# Board.net
KiCad netlist of a schematic drawn in EAGLE
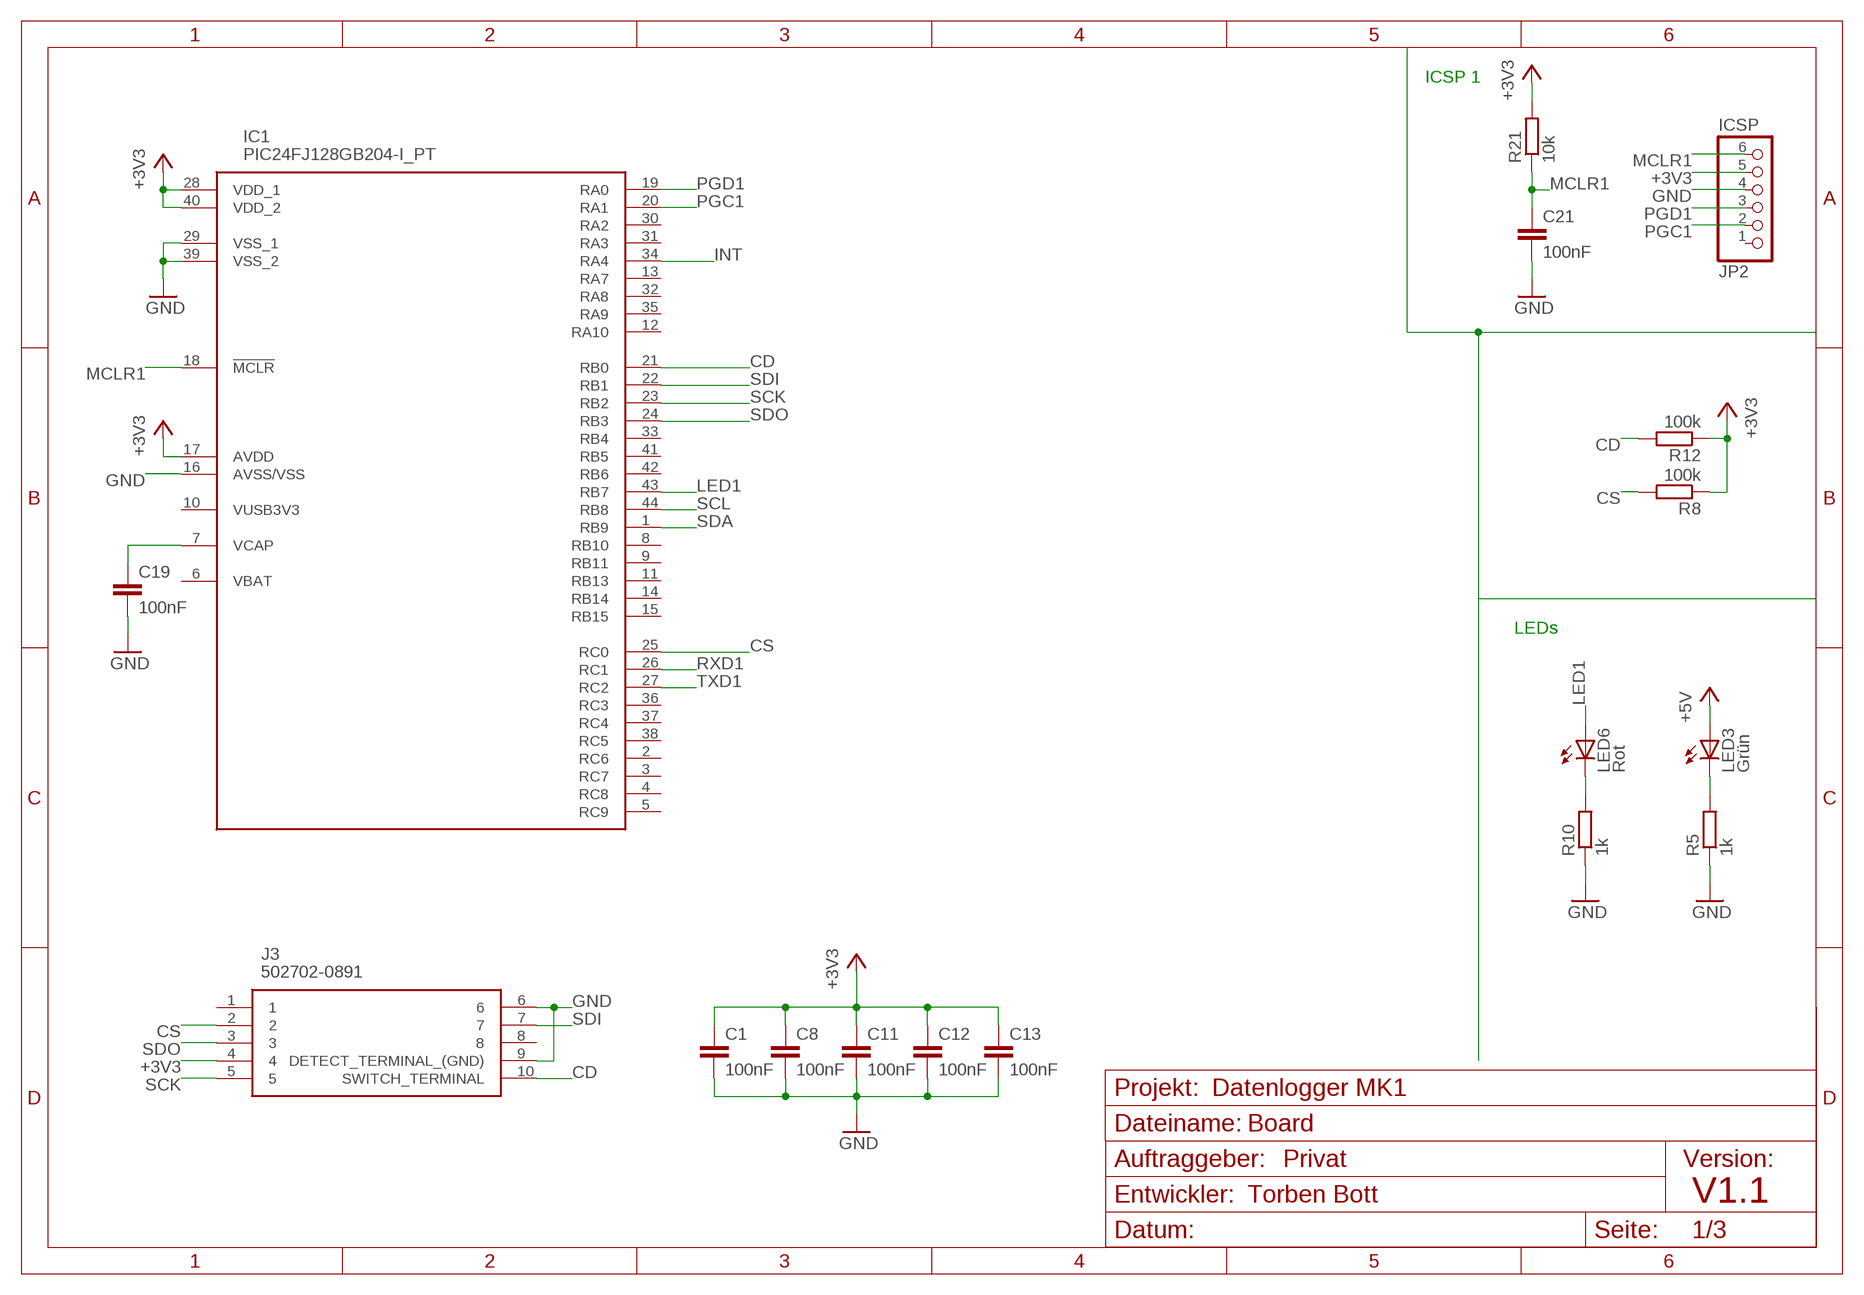
[diagram p0: schematic, sheet 1]
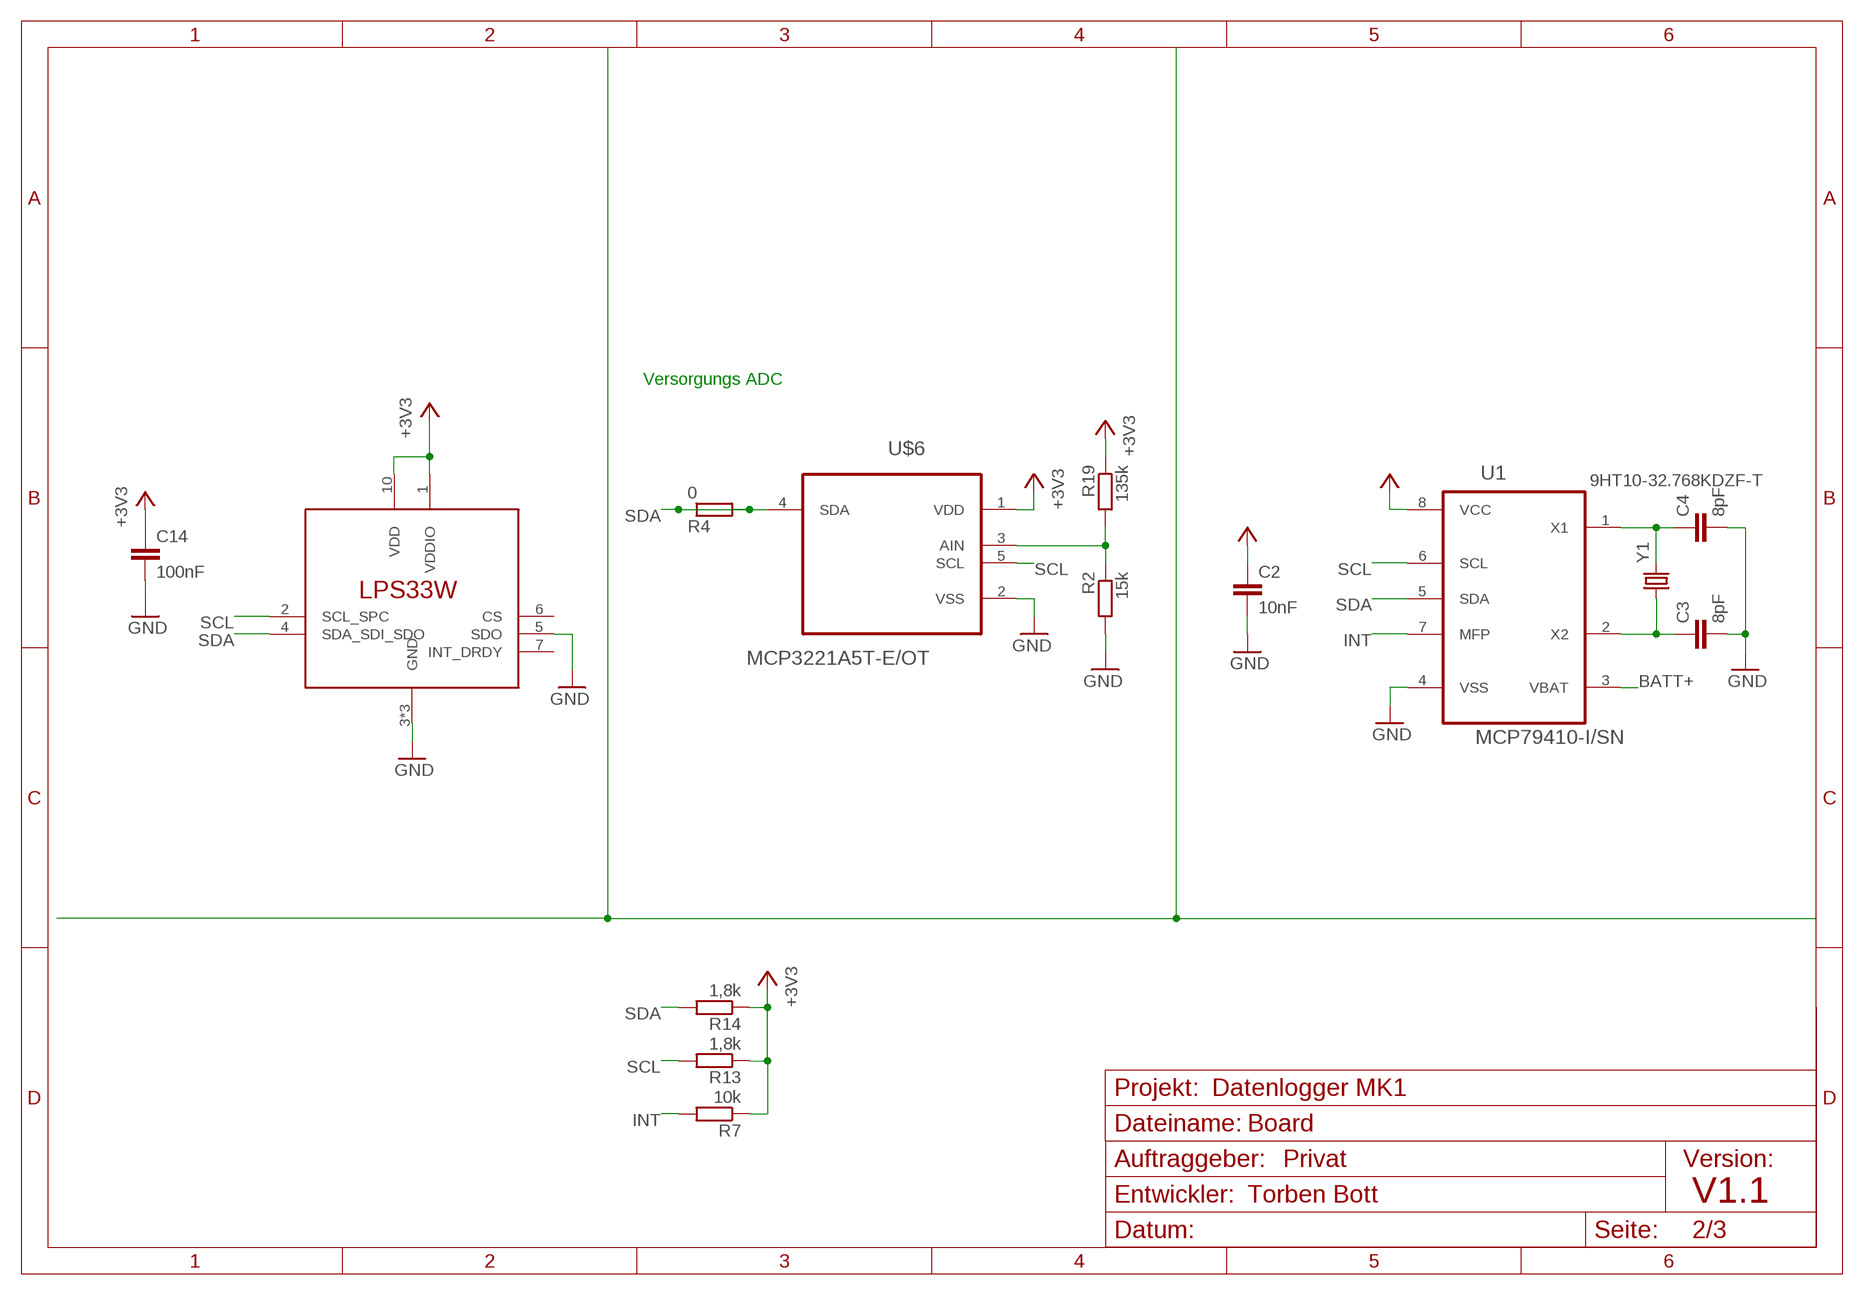
[diagram p1: schematic, sheet 2]
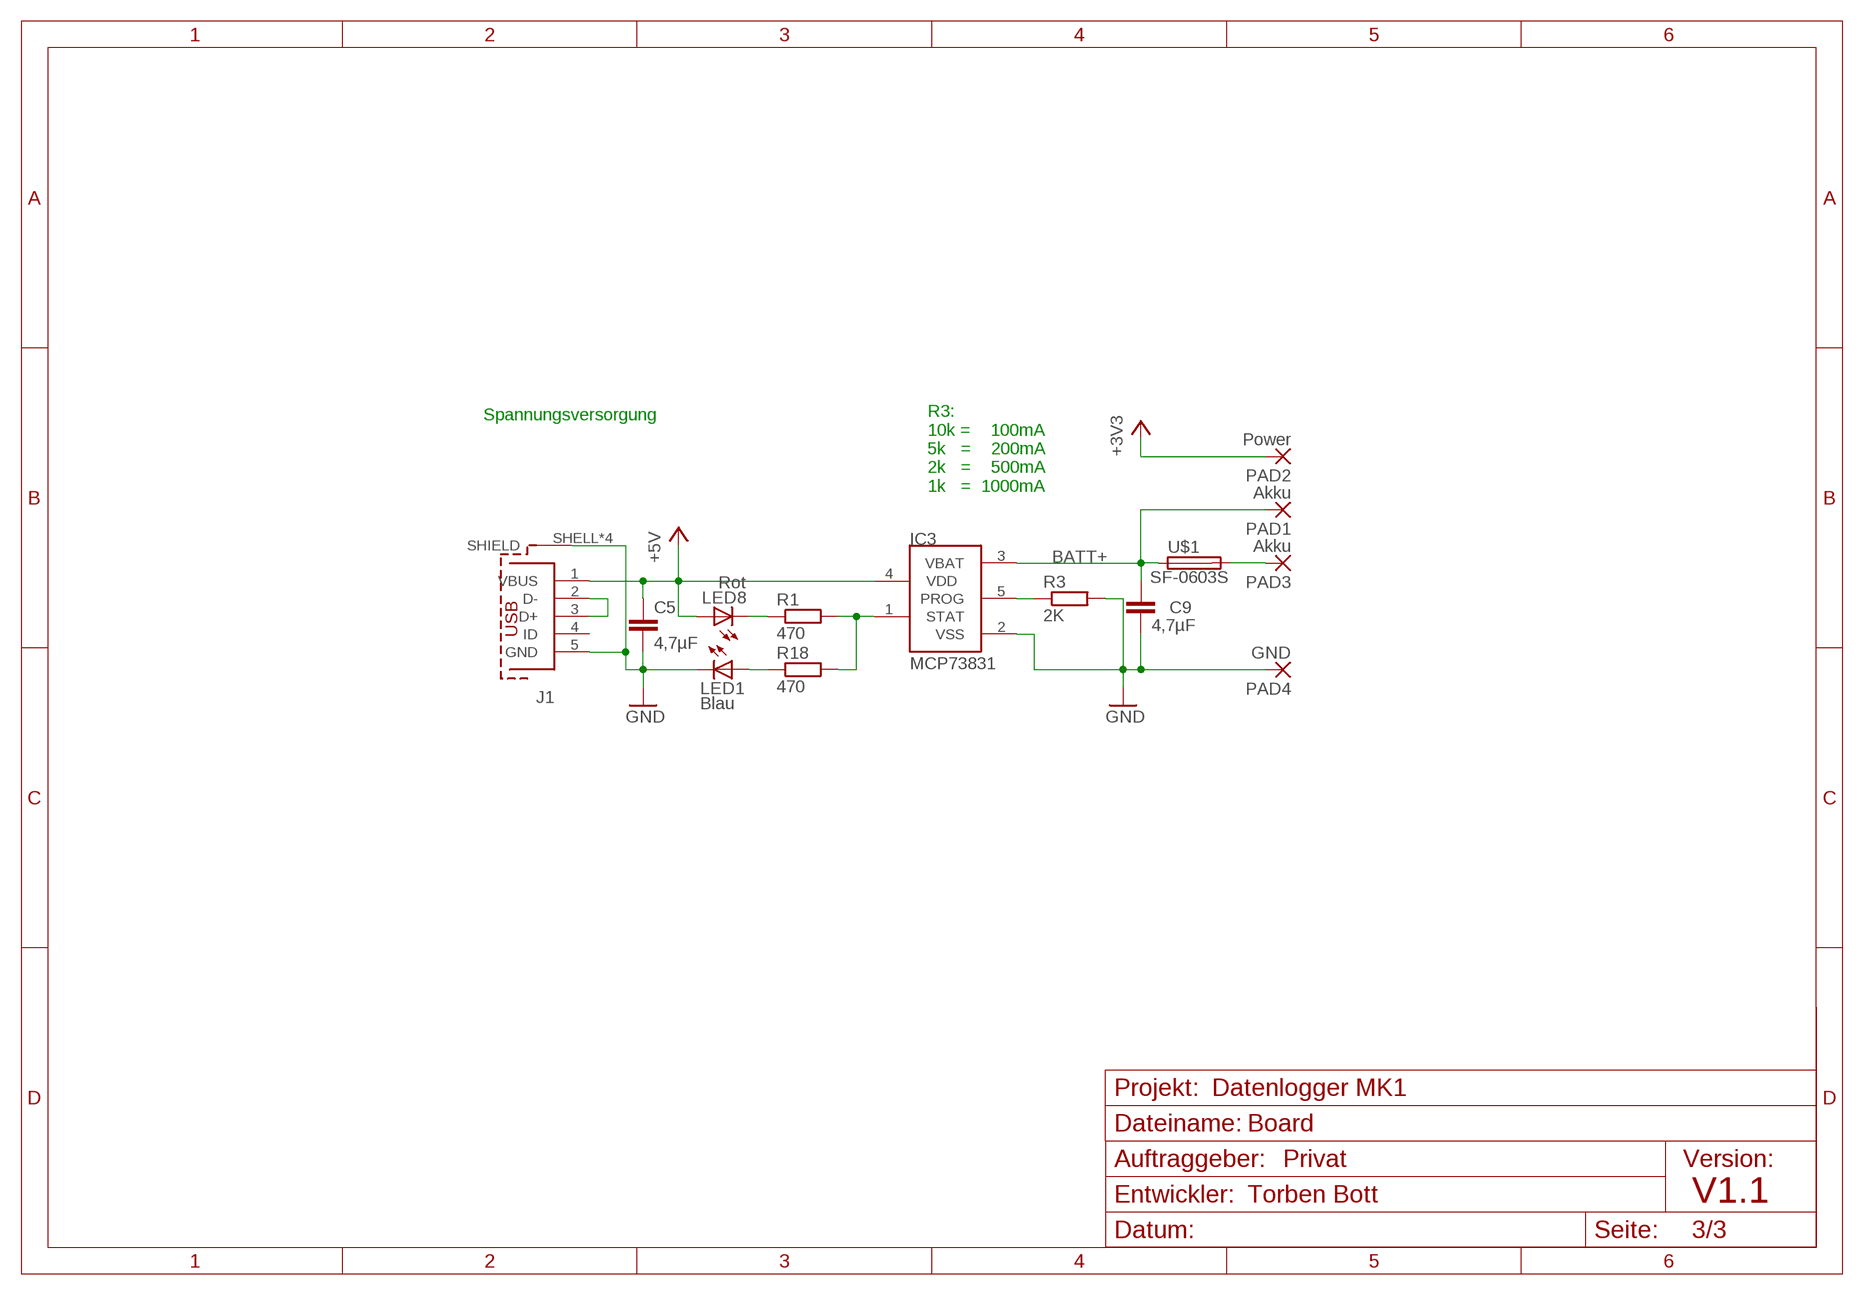
[diagram p2: schematic, sheet 3]

(export (version "E")
  (design (tool "Eeschema 10.0.6"))
  (components
    (comp (ref "C1")
      (value "100nF")
      (footprint "eagle-import:C0805")
      (libsource (lib "eagle-import") (part "rcl_334_C-EUC0805"))
    )
    (comp (ref "C8")
      (value "100nF")
      (footprint "eagle-import:C0805")
      (libsource (lib "eagle-import") (part "rcl_334_C-EUC0805"))
    )
    (comp (ref "C11")
      (value "100nF")
      (footprint "eagle-import:C0805")
      (libsource (lib "eagle-import") (part "rcl_334_C-EUC0805"))
    )
    (comp (ref "C12")
      (value "100nF")
      (footprint "eagle-import:C0805")
      (libsource (lib "eagle-import") (part "rcl_334_C-EUC0805"))
    )
    (comp (ref "C13")
      (value "100nF")
      (footprint "eagle-import:C0805")
      (libsource (lib "eagle-import") (part "rcl_334_C-EUC0805"))
    )
    (comp (ref "C19")
      (value "100nF")
      (footprint "eagle-import:C0805")
      (libsource (lib "eagle-import") (part "rcl_334_C-EUC0805"))
    )
    (comp (ref "C21")
      (value "100nF")
      (footprint "eagle-import:C0805")
      (libsource (lib "eagle-import") (part "rcl_334_C-EUC0805"))
    )
    (comp (ref "IC1")
      (value "PIC24FJ128GB204-I_PT")
      (footprint "eagle-import:QFP80P1200X1200X120-44N")
      (fields
        (field (name "MANUFACTURER_PART_NUMBER") "PIC24FJ128GB204-I/PT")
        (field (name "MOUSER_PART_NUMBER") "579-P24FJ128GB204IPT")
      )
      (libsource (lib "eagle-import") (part "PIC24FJ128GB204-I_PT"))
    )
    (comp (ref "J3")
      (value "502702-0891")
      (footprint "eagle-import:502702-0891")
      (fields (field (name "MOUSER_PART_NUMBER") "538-502702-0891"))
      (libsource (lib "eagle-import") (part "502702-0891"))
    )
    (comp (ref "JP2")
      (value "ICSP")
      (footprint "eagle-import:1X06_90")
      (libsource (lib "eagle-import") (part "PINHD-1X6/90"))
    )
    (comp (ref "LED3")
      (value "Grün")
      (footprint "eagle-import:CHIPLED_0805")
      (libsource (lib "eagle-import") (part "led_259_LEDCHIPLED_0805"))
    )
    (comp (ref "LED6")
      (value "Rot")
      (footprint "eagle-import:CHIPLED_0805")
      (libsource (lib "eagle-import") (part "led_259_LEDCHIPLED_0805"))
    )
    (comp (ref "R5")
      (value "1k")
      (footprint "eagle-import:R0805")
      (libsource (lib "eagle-import") (part "rcl_334_R-EU_R0805"))
    )
    (comp (ref "R8")
      (value "100k")
      (footprint "eagle-import:R0805")
      (libsource (lib "eagle-import") (part "rcl_334_R-EU_R0805"))
    )
    (comp (ref "R10")
      (value "1k")
      (footprint "eagle-import:R0805")
      (libsource (lib "eagle-import") (part "rcl_334_R-EU_R0805"))
    )
    (comp (ref "R12")
      (value "100k")
      (footprint "eagle-import:R0805")
      (libsource (lib "eagle-import") (part "rcl_334_R-EU_R0805"))
    )
    (comp (ref "R21")
      (value "10k")
      (footprint "eagle-import:R0805")
      (libsource (lib "eagle-import") (part "rcl_334_R-EU_R0805"))
    )
    (comp (ref "C2")
      (value "10nF")
      (footprint "eagle-import:C0805")
      (libsource (lib "eagle-import") (part "rcl_334_C-EUC0805"))
    )
    (comp (ref "C3")
      (value "8pF")
      (footprint "eagle-import:C0805")
      (libsource (lib "eagle-import") (part "rcl_334_C-EUC0805"))
    )
    (comp (ref "C4")
      (value "8pF")
      (footprint "eagle-import:C0805")
      (libsource (lib "eagle-import") (part "rcl_334_C-EUC0805"))
    )
    (comp (ref "C14")
      (value "100nF")
      (footprint "eagle-import:C0805")
      (libsource (lib "eagle-import") (part "rcl_334_C-EUC0805"))
    )
    (comp (ref "R2")
      (value "15k")
      (footprint "eagle-import:R0805")
      (libsource (lib "eagle-import") (part "rcl_334_R-EU_R0805"))
    )
    (comp (ref "R4")
      (value "0")
      (footprint "eagle-import:R0805")
      (libsource (lib "eagle-import") (part "rcl_334_R-EU_R0805"))
    )
    (comp (ref "R7")
      (value "10k")
      (footprint "eagle-import:R0805")
      (libsource (lib "eagle-import") (part "rcl_334_R-EU_R0805"))
    )
    (comp (ref "R13")
      (value "1,8k")
      (footprint "eagle-import:R0805")
      (libsource (lib "eagle-import") (part "rcl_334_R-EU_R0805"))
    )
    (comp (ref "R14")
      (value "1,8k")
      (footprint "eagle-import:R0805")
      (libsource (lib "eagle-import") (part "rcl_334_R-EU_R0805"))
    )
    (comp (ref "R19")
      (value "135k")
      (footprint "eagle-import:R0805")
      (libsource (lib "eagle-import") (part "rcl_334_R-EU_R0805"))
    )
    (comp (ref "U$6")
      (value "MCP3221A5T-E/OT")
      (footprint "eagle-import:SOT95P270X145-5N")
      (libsource (lib "eagle-import") (part "MCP3221A5T-E/OT"))
    )
    (comp (ref "U$7")
      (value "LPS33W")
      (footprint "eagle-import:CCLGA10L")
      (libsource (lib "eagle-import") (part "LPS33W"))
    )
    (comp (ref "U1")
      (value "MCP79410-I/SN")
      (footprint "eagle-import:SOIC127P600X175-8N")
      (fields (field (name "MPN") "MCP79410-I/SN "))
      (libsource (lib "eagle-import") (part "MCP79410-I/SN"))
    )
    (comp (ref "Y1")
      (value "9HT10-32.768KDZF-T")
      (footprint "eagle-import:9HT1032768KEZFT")
      (fields (field (name "MOUSER_PART_NUMBER") "717-9HT10-32.768KDZF"))
      (libsource (lib "eagle-import") (part "9HT10-32.768KDZF-T"))
    )
    (comp (ref "C5")
      (value "4,7µF")
      (footprint "eagle-import:C0805")
      (libsource (lib "eagle-import") (part "C-EUC0805"))
    )
    (comp (ref "C9")
      (value "4,7µF")
      (footprint "eagle-import:C0805")
      (libsource (lib "eagle-import") (part "C-EUC0805"))
    )
    (comp (ref "IC3")
      (value "MCP73831")
      (footprint "eagle-import:SOT23-5L")
      (libsource (lib "eagle-import") (part "MCP73831"))
    )
    (comp (ref "J1")
      (value "629105136821")
      (footprint "eagle-import:629105136821")
      (libsource (lib "eagle-import") (part "629105136821"))
    )
    (comp (ref "LED1")
      (value "Blau")
      (footprint "eagle-import:CHIPLED_0805")
      (libsource (lib "eagle-import") (part "LEDCHIPLED_0805"))
    )
    (comp (ref "LED8")
      (value "Rot")
      (footprint "eagle-import:CHIPLED_0805")
      (libsource (lib "eagle-import") (part "LEDCHIPLED_0805"))
    )
    (comp (ref "PAD1")
      (value "Akku")
      (footprint "eagle-import:5-1,8")
      (libsource (lib "eagle-import") (part "WIREPADSMD5-1,8"))
    )
    (comp (ref "PAD2")
      (value "Power")
      (footprint "eagle-import:5-1,8")
      (libsource (lib "eagle-import") (part "WIREPADSMD5-1,8"))
    )
    (comp (ref "PAD3")
      (value "Akku")
      (footprint "eagle-import:5-1,8")
      (libsource (lib "eagle-import") (part "WIREPADSMD5-1,8"))
    )
    (comp (ref "PAD4")
      (value "GND")
      (footprint "eagle-import:5-1,8")
      (libsource (lib "eagle-import") (part "WIREPADSMD5-1,8"))
    )
    (comp (ref "R1")
      (value "470")
      (footprint "eagle-import:R0805")
      (libsource (lib "eagle-import") (part "R-EU_R0805"))
    )
    (comp (ref "R3")
      (value "2K")
      (footprint "eagle-import:R0805")
      (libsource (lib "eagle-import") (part "R-EU_R0805"))
    )
    (comp (ref "R18")
      (value "470")
      (footprint "eagle-import:R0805")
      (libsource (lib "eagle-import") (part "R-EU_R0805"))
    )
    (comp (ref "U$1")
      (value "SF-0603S")
      (footprint "eagle-import:R0603")
      (libsource (lib "eagle-import") (part "SF-0603S"))
    )
  )
  (nets
    (net (code "1") (name "+3V3") (class "Default")
      (node (ref "C1") (pin "1") (pinfunction "1_1") (pintype "passive"))
      (node (ref "C11") (pin "1") (pinfunction "1_1") (pintype "passive"))
      (node (ref "C12") (pin "1") (pinfunction "1_1") (pintype "passive"))
      (node (ref "C13") (pin "1") (pinfunction "1_1") (pintype "passive"))
      (node (ref "C14") (pin "1") (pinfunction "1_1") (pintype "passive"))
      (node (ref "C2") (pin "1") (pinfunction "1_1") (pintype "passive"))
      (node (ref "C8") (pin "1") (pinfunction "1_1") (pintype "passive"))
      (node (ref "IC1") (pin "17") (pinfunction "AVDD_17") (pintype "power_in"))
      (node (ref "IC1") (pin "28") (pinfunction "VDD_1_28") (pintype "power_in"))
      (node (ref "IC1") (pin "40") (pinfunction "VDD_2_40") (pintype "power_in"))
      (node (ref "J3") (pin "4") (pinfunction "4_4") (pintype "bidirectional"))
      (node (ref "JP2") (pin "5") (pinfunction "5_5") (pintype "passive"))
      (node (ref "PAD2") (pin "1") (pinfunction "P_1") (pintype "passive"))
      (node (ref "R12") (pin "1") (pinfunction "1_1") (pintype "passive"))
      (node (ref "R13") (pin "1") (pinfunction "1_1") (pintype "passive"))
      (node (ref "R14") (pin "1") (pinfunction "1_1") (pintype "passive"))
      (node (ref "R19") (pin "1") (pinfunction "1_1") (pintype "passive"))
      (node (ref "R21") (pin "2") (pinfunction "2_2") (pintype "passive"))
      (node (ref "R7") (pin "1") (pinfunction "1_1") (pintype "passive"))
      (node (ref "R8") (pin "1") (pinfunction "1_1") (pintype "passive"))
      (node (ref "U$6") (pin "1") (pinfunction "VDD_1") (pintype "power_in"))
      (node (ref "U$7") (pin "1") (pinfunction "VDDIO_1") (pintype "power_in"))
      (node (ref "U$7") (pin "10") (pinfunction "VDD_10") (pintype "power_in"))
      (node (ref "U1") (pin "8") (pinfunction "VCC_8") (pintype "power_in"))
    )
    (net (code "2") (name "+5V") (class "Default")
      (node (ref "C5") (pin "1") (pinfunction "1_1") (pintype "passive"))
      (node (ref "IC3") (pin "4") (pinfunction "VDD_4") (pintype "bidirectional"))
      (node (ref "J1") (pin "1") (pinfunction "VBUS_1") (pintype "passive"))
      (node (ref "LED3") (pin "A") (pinfunction "A_A") (pintype "passive"))
      (node (ref "LED8") (pin "A") (pinfunction "A_A") (pintype "passive"))
    )
    (net (code "3") (name "BATT+") (class "Default")
      (node (ref "C9") (pin "1") (pinfunction "1_1") (pintype "passive"))
      (node (ref "IC3") (pin "3") (pinfunction "VBAT_3") (pintype "bidirectional"))
      (node (ref "PAD1") (pin "1") (pinfunction "P_1") (pintype "passive"))
      (node (ref "U$1") (pin "1") (pinfunction "1_1") (pintype "passive"))
      (node (ref "U1") (pin "3") (pinfunction "VBAT_3") (pintype "power_in"))
    )
    (net (code "4") (name "CD") (class "Default")
      (node (ref "IC1") (pin "21") (pinfunction "RB0_21") (pintype "bidirectional"))
      (node (ref "J3") (pin "10") (pinfunction "SWITCH_TERMINAL_10") (pintype "bidirectional"))
      (node (ref "R12") (pin "2") (pinfunction "2_2") (pintype "passive"))
    )
    (net (code "5") (name "CS") (class "Default")
      (node (ref "IC1") (pin "25") (pinfunction "RC0_25") (pintype "bidirectional"))
      (node (ref "J3") (pin "2") (pinfunction "2_2") (pintype "bidirectional"))
      (node (ref "R8") (pin "2") (pinfunction "2_2") (pintype "passive"))
    )
    (net (code "6") (name "GND") (class "Default")
      (node (ref "C1") (pin "2") (pinfunction "2_2") (pintype "passive"))
      (node (ref "C11") (pin "2") (pinfunction "2_2") (pintype "passive"))
      (node (ref "C12") (pin "2") (pinfunction "2_2") (pintype "passive"))
      (node (ref "C13") (pin "2") (pinfunction "2_2") (pintype "passive"))
      (node (ref "C14") (pin "2") (pinfunction "2_2") (pintype "passive"))
      (node (ref "C19") (pin "2") (pinfunction "2_2") (pintype "passive"))
      (node (ref "C2") (pin "2") (pinfunction "2_2") (pintype "passive"))
      (node (ref "C21") (pin "2") (pinfunction "2_2") (pintype "passive"))
      (node (ref "C3") (pin "2") (pinfunction "2_2") (pintype "passive"))
      (node (ref "C4") (pin "2") (pinfunction "2_2") (pintype "passive"))
      (node (ref "C5") (pin "2") (pinfunction "2_2") (pintype "passive"))
      (node (ref "C8") (pin "2") (pinfunction "2_2") (pintype "passive"))
      (node (ref "C9") (pin "2") (pinfunction "2_2") (pintype "passive"))
      (node (ref "IC1") (pin "16") (pinfunction "AVSS/VSS_16") (pintype "power_in"))
      (node (ref "IC1") (pin "29") (pinfunction "VSS_1_29") (pintype "power_in"))
      (node (ref "IC1") (pin "39") (pinfunction "VSS_2_39") (pintype "power_in"))
      (node (ref "IC3") (pin "2") (pinfunction "VSS_2") (pintype "bidirectional"))
      (node (ref "J1") (pin "5") (pinfunction "GND_5") (pintype "passive"))
      (node (ref "J1") (pin "SHELL") (pinfunction "SHIELD_SHELL") (pintype "passive"))
      (node (ref "J1") (pin "SHELL1") (pinfunction "SHIELD_SHELL1") (pintype "passive"))
      (node (ref "J1") (pin "SHELL2") (pinfunction "SHIELD_SHELL2") (pintype "passive"))
      (node (ref "J1") (pin "SHELL3") (pinfunction "SHIELD_SHELL3") (pintype "passive"))
      (node (ref "J3") (pin "6") (pinfunction "6_6") (pintype "bidirectional"))
      (node (ref "J3") (pin "9") (pinfunction "DETECT_TERMINAL_(GND)_9") (pintype "bidirectional"))
      (node (ref "JP2") (pin "4") (pinfunction "4_4") (pintype "passive"))
      (node (ref "LED1") (pin "C") (pinfunction "C_C") (pintype "passive"))
      (node (ref "PAD4") (pin "1") (pinfunction "P_1") (pintype "passive"))
      (node (ref "R10") (pin "1") (pinfunction "1_1") (pintype "passive"))
      (node (ref "R2") (pin "2") (pinfunction "2_2") (pintype "passive"))
      (node (ref "R3") (pin "2") (pinfunction "2_2") (pintype "passive"))
      (node (ref "R5") (pin "1") (pinfunction "1_1") (pintype "passive"))
      (node (ref "U$6") (pin "2") (pinfunction "VSS_2") (pintype "passive"))
      (node (ref "U$7") (pin "3") (pinfunction "GND_3") (pintype "power_in"))
      (node (ref "U$7") (pin "5") (pinfunction "SDO_5") (pintype "bidirectional"))
      (node (ref "U$7") (pin "8") (pinfunction "GND_8") (pintype "power_in"))
      (node (ref "U$7") (pin "9") (pinfunction "GND_9") (pintype "power_in"))
      (node (ref "U1") (pin "4") (pinfunction "VSS_4") (pintype "power_in"))
    )
    (net (code "7") (name "INT") (class "Default")
      (node (ref "IC1") (pin "34") (pinfunction "RA4_34") (pintype "bidirectional"))
      (node (ref "R7") (pin "2") (pinfunction "2_2") (pintype "passive"))
      (node (ref "U1") (pin "7") (pinfunction "MFP_7") (pintype "input"))
    )
    (net (code "8") (name "LED1") (class "Default")
      (node (ref "IC1") (pin "43") (pinfunction "RB7_43") (pintype "bidirectional"))
      (node (ref "LED6") (pin "A") (pinfunction "A_A") (pintype "passive"))
    )
    (net (code "9") (name "MCLR1") (class "Default")
      (node (ref "C21") (pin "1") (pinfunction "1_1") (pintype "passive"))
      (node (ref "IC1") (pin "18") (pinfunction "~{MCLR}_18") (pintype "bidirectional"))
      (node (ref "JP2") (pin "6") (pinfunction "6_6") (pintype "passive"))
      (node (ref "R21") (pin "1") (pinfunction "1_1") (pintype "passive"))
    )
    (net (code "10") (name "Net-(IC1-VCAP)") (class "Default")
      (node (ref "C19") (pin "1") (pinfunction "1_1") (pintype "passive"))
      (node (ref "IC1") (pin "7") (pinfunction "VCAP_7") (pintype "bidirectional"))
    )
    (net (code "11") (name "Net-(IC3-PROG)") (class "Default")
      (node (ref "IC3") (pin "5") (pinfunction "PROG_5") (pintype "bidirectional"))
      (node (ref "R3") (pin "1") (pinfunction "1_1") (pintype "passive"))
    )
    (net (code "12") (name "Net-(IC3-STAT)") (class "Default")
      (node (ref "IC3") (pin "1") (pinfunction "STAT_1") (pintype "bidirectional"))
      (node (ref "R1") (pin "2") (pinfunction "2_2") (pintype "passive"))
      (node (ref "R18") (pin "2") (pinfunction "2_2") (pintype "passive"))
    )
    (net (code "13") (name "Net-(J1-D+)") (class "Default")
      (node (ref "J1") (pin "2") (pinfunction "D-_2") (pintype "passive"))
      (node (ref "J1") (pin "3") (pinfunction "D+_3") (pintype "passive"))
    )
    (net (code "14") (name "Net-(LED1-PadA)") (class "Default")
      (node (ref "LED1") (pin "A") (pinfunction "A_A") (pintype "passive"))
      (node (ref "R18") (pin "1") (pinfunction "1_1") (pintype "passive"))
    )
    (net (code "15") (name "Net-(LED3-PadC)") (class "Default")
      (node (ref "LED3") (pin "C") (pinfunction "C_C") (pintype "passive"))
      (node (ref "R5") (pin "2") (pinfunction "2_2") (pintype "passive"))
    )
    (net (code "16") (name "Net-(LED6-PadC)") (class "Default")
      (node (ref "LED6") (pin "C") (pinfunction "C_C") (pintype "passive"))
      (node (ref "R10") (pin "2") (pinfunction "2_2") (pintype "passive"))
    )
    (net (code "17") (name "Net-(LED8-PadC)") (class "Default")
      (node (ref "LED8") (pin "C") (pinfunction "C_C") (pintype "passive"))
      (node (ref "R1") (pin "1") (pinfunction "1_1") (pintype "passive"))
    )
    (net (code "18") (name "Net-(PAD3-P)") (class "Default")
      (node (ref "PAD3") (pin "1") (pinfunction "P_1") (pintype "passive"))
      (node (ref "U$1") (pin "2") (pinfunction "2_2") (pintype "passive"))
    )
    (net (code "19") (name "Net-(U$6-AIN)") (class "Default")
      (node (ref "R19") (pin "2") (pinfunction "2_2") (pintype "passive"))
      (node (ref "R2") (pin "1") (pinfunction "1_1") (pintype "passive"))
      (node (ref "U$6") (pin "3") (pinfunction "AIN_3") (pintype "input"))
    )
    (net (code "20") (name "Net-(U1-X1)") (class "Default")
      (node (ref "C4") (pin "1") (pinfunction "1_1") (pintype "passive"))
      (node (ref "U1") (pin "1") (pinfunction "X1_1") (pintype "input"))
      (node (ref "Y1") (pin "2") (pinfunction "2_2") (pintype "passive"))
    )
    (net (code "21") (name "Net-(U1-X2)") (class "Default")
      (node (ref "C3") (pin "1") (pinfunction "1_1") (pintype "passive"))
      (node (ref "U1") (pin "2") (pinfunction "X2_2") (pintype "output"))
      (node (ref "Y1") (pin "1") (pinfunction "1_1") (pintype "passive"))
    )
    (net (code "22") (name "PGC1") (class "Default")
      (node (ref "IC1") (pin "20") (pinfunction "RA1_20") (pintype "bidirectional"))
      (node (ref "JP2") (pin "2") (pinfunction "2_2") (pintype "passive"))
    )
    (net (code "23") (name "PGD1") (class "Default")
      (node (ref "IC1") (pin "19") (pinfunction "RA0_19") (pintype "bidirectional"))
      (node (ref "JP2") (pin "3") (pinfunction "3_3") (pintype "passive"))
    )
    (net (code "24") (name "RXD1") (class "Default")
      (node (ref "IC1") (pin "26") (pinfunction "RC1_26") (pintype "bidirectional"))
    )
    (net (code "25") (name "SCK") (class "Default")
      (node (ref "IC1") (pin "23") (pinfunction "RB2_23") (pintype "bidirectional"))
      (node (ref "J3") (pin "5") (pinfunction "5_5") (pintype "bidirectional"))
    )
    (net (code "26") (name "SCL") (class "Default")
      (node (ref "IC1") (pin "44") (pinfunction "RB8_44") (pintype "bidirectional"))
      (node (ref "R13") (pin "2") (pinfunction "2_2") (pintype "passive"))
      (node (ref "U$6") (pin "5") (pinfunction "SCL_5") (pintype "input"))
      (node (ref "U$7") (pin "2") (pinfunction "SCL_SPC_2") (pintype "input"))
      (node (ref "U1") (pin "6") (pinfunction "SCL_6") (pintype "input"))
    )
    (net (code "27") (name "SDA") (class "Default")
      (node (ref "IC1") (pin "1") (pinfunction "RB9_1") (pintype "bidirectional"))
      (node (ref "R14") (pin "2") (pinfunction "2_2") (pintype "passive"))
      (node (ref "R4") (pin "1") (pinfunction "1_1") (pintype "passive"))
      (node (ref "R4") (pin "2") (pinfunction "2_2") (pintype "passive"))
      (node (ref "U$6") (pin "4") (pinfunction "SDA_4") (pintype "bidirectional"))
      (node (ref "U$7") (pin "4") (pinfunction "SDA_SDI_SDO_4") (pintype "bidirectional"))
      (node (ref "U1") (pin "5") (pinfunction "SDA_5") (pintype "bidirectional"))
    )
    (net (code "28") (name "SDI") (class "Default")
      (node (ref "IC1") (pin "22") (pinfunction "RB1_22") (pintype "bidirectional"))
      (node (ref "J3") (pin "7") (pinfunction "7_7") (pintype "bidirectional"))
    )
    (net (code "29") (name "SDO") (class "Default")
      (node (ref "IC1") (pin "24") (pinfunction "RB3_24") (pintype "bidirectional"))
      (node (ref "J3") (pin "3") (pinfunction "3_3") (pintype "bidirectional"))
    )
    (net (code "30") (name "TXD1") (class "Default")
      (node (ref "IC1") (pin "27") (pinfunction "RC2_27") (pintype "bidirectional"))
    )
    (net (code "31") (name "unconnected-(IC1-RA2-Pad30)") (class "Default")
      (node (ref "IC1") (pin "30") (pinfunction "RA2_30") (pintype "bidirectional"))
    )
    (net (code "32") (name "unconnected-(IC1-RA3-Pad31)") (class "Default")
      (node (ref "IC1") (pin "31") (pinfunction "RA3_31") (pintype "bidirectional"))
    )
    (net (code "33") (name "unconnected-(IC1-RA7-Pad13)") (class "Default")
      (node (ref "IC1") (pin "13") (pinfunction "RA7_13") (pintype "bidirectional"))
    )
    (net (code "34") (name "unconnected-(IC1-RA8-Pad32)") (class "Default")
      (node (ref "IC1") (pin "32") (pinfunction "RA8_32") (pintype "bidirectional"))
    )
    (net (code "35") (name "unconnected-(IC1-RA9-Pad35)") (class "Default")
      (node (ref "IC1") (pin "35") (pinfunction "RA9_35") (pintype "bidirectional"))
    )
    (net (code "36") (name "unconnected-(IC1-RA10-Pad12)") (class "Default")
      (node (ref "IC1") (pin "12") (pinfunction "RA10_12") (pintype "bidirectional"))
    )
    (net (code "37") (name "unconnected-(IC1-RB4-Pad33)") (class "Default")
      (node (ref "IC1") (pin "33") (pinfunction "RB4_33") (pintype "bidirectional"))
    )
    (net (code "38") (name "unconnected-(IC1-RB5-Pad41)") (class "Default")
      (node (ref "IC1") (pin "41") (pinfunction "RB5_41") (pintype "bidirectional"))
    )
    (net (code "39") (name "unconnected-(IC1-RB6-Pad42)") (class "Default")
      (node (ref "IC1") (pin "42") (pinfunction "RB6_42") (pintype "bidirectional"))
    )
    (net (code "40") (name "unconnected-(IC1-RB10-Pad8)") (class "Default")
      (node (ref "IC1") (pin "8") (pinfunction "RB10_8") (pintype "bidirectional"))
    )
    (net (code "41") (name "unconnected-(IC1-RB11-Pad9)") (class "Default")
      (node (ref "IC1") (pin "9") (pinfunction "RB11_9") (pintype "bidirectional"))
    )
    (net (code "42") (name "unconnected-(IC1-RB13-Pad11)") (class "Default")
      (node (ref "IC1") (pin "11") (pinfunction "RB13_11") (pintype "bidirectional"))
    )
    (net (code "43") (name "unconnected-(IC1-RB14-Pad14)") (class "Default")
      (node (ref "IC1") (pin "14") (pinfunction "RB14_14") (pintype "bidirectional"))
    )
    (net (code "44") (name "unconnected-(IC1-RB15-Pad15)") (class "Default")
      (node (ref "IC1") (pin "15") (pinfunction "RB15_15") (pintype "bidirectional"))
    )
    (net (code "45") (name "unconnected-(IC1-RC3-Pad36)") (class "Default")
      (node (ref "IC1") (pin "36") (pinfunction "RC3_36") (pintype "bidirectional"))
    )
    (net (code "46") (name "unconnected-(IC1-RC4-Pad37)") (class "Default")
      (node (ref "IC1") (pin "37") (pinfunction "RC4_37") (pintype "bidirectional"))
    )
    (net (code "47") (name "unconnected-(IC1-RC5-Pad38)") (class "Default")
      (node (ref "IC1") (pin "38") (pinfunction "RC5_38") (pintype "bidirectional"))
    )
    (net (code "48") (name "unconnected-(IC1-RC6-Pad2)") (class "Default")
      (node (ref "IC1") (pin "2") (pinfunction "RC6_2") (pintype "bidirectional"))
    )
    (net (code "49") (name "unconnected-(IC1-RC7-Pad3)") (class "Default")
      (node (ref "IC1") (pin "3") (pinfunction "RC7_3") (pintype "bidirectional"))
    )
    (net (code "50") (name "unconnected-(IC1-RC8-Pad4)") (class "Default")
      (node (ref "IC1") (pin "4") (pinfunction "RC8_4") (pintype "bidirectional"))
    )
    (net (code "51") (name "unconnected-(IC1-RC9-Pad5)") (class "Default")
      (node (ref "IC1") (pin "5") (pinfunction "RC9_5") (pintype "bidirectional"))
    )
    (net (code "52") (name "unconnected-(IC1-VBAT-Pad6)") (class "Default")
      (node (ref "IC1") (pin "6") (pinfunction "VBAT_6") (pintype "bidirectional"))
    )
    (net (code "53") (name "unconnected-(IC1-VUSB3V3-Pad10)") (class "Default")
      (node (ref "IC1") (pin "10") (pinfunction "VUSB3V3_10") (pintype "bidirectional"))
    )
    (net (code "54") (name "unconnected-(J1-ID-Pad4)") (class "Default")
      (node (ref "J1") (pin "4") (pinfunction "ID_4") (pintype "passive"))
    )
    (net (code "55") (name "unconnected-(J3-Pad1)") (class "Default")
      (node (ref "J3") (pin "1") (pinfunction "1_1") (pintype "bidirectional"))
    )
    (net (code "56") (name "unconnected-(J3-Pad8)") (class "Default")
      (node (ref "J3") (pin "8") (pinfunction "8_8") (pintype "bidirectional"))
    )
    (net (code "57") (name "unconnected-(JP2-Pad1)") (class "Default")
      (node (ref "JP2") (pin "1") (pinfunction "1_1") (pintype "passive"))
    )
    (net (code "58") (name "unconnected-(U$7-CS-Pad6)") (class "Default")
      (node (ref "U$7") (pin "6") (pinfunction "CS_6") (pintype "bidirectional"))
    )
    (net (code "59") (name "unconnected-(U$7-INT_DRDY-Pad7)") (class "Default")
      (node (ref "U$7") (pin "7") (pinfunction "INT_DRDY_7") (pintype "output"))
    )
  )
)
